# VT_8S_RHS_Bot_V0_1.net
KiCad netlist of a schematic drawn in Altium Designer
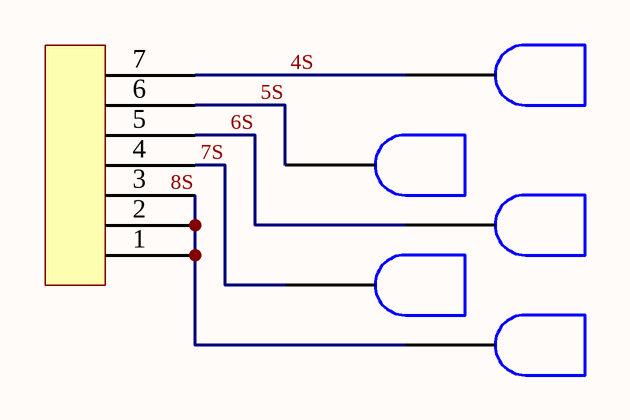
[diagram p0: VT 8S RHS Bot V0.1.SchDoc]

(export (version "E")
  (design (tool "Eeschema 10.0.6"))
  (components
    (comp (ref "J1")
      (value "Voltage Tap")
      (footprint "Voltage Tap")
      (libsource (lib "Voltage Taps V0.1") (part "Voltage Tap"))
    )
    (comp (ref "J2")
      (value "Voltage Tap")
      (footprint "Voltage Tap")
      (libsource (lib "Voltage Taps V0.1") (part "Voltage Tap"))
    )
    (comp (ref "J3")
      (value "Voltage Tap")
      (footprint "Voltage Tap")
      (libsource (lib "Voltage Taps V0.1") (part "Voltage Tap"))
    )
    (comp (ref "J4")
      (value "Voltage Tap")
      (footprint "Voltage Tap")
      (libsource (lib "Voltage Taps V0.1") (part "Voltage Tap"))
    )
    (comp (ref "J5")
      (value "84953-7-FPC")
      (footprint "84953-7 - FPC")
      (description "FPC Connectors, Flex-to-Board, 7 Position, .039 in [1 mm] Centerline, FPC Side Connector")
      (libsource (lib "TE_Con") (part "84953-7-FPC"))
    )
    (comp (ref "J6")
      (value "Voltage Tap")
      (footprint "Voltage Tap")
      (libsource (lib "Voltage Taps V0.1") (part "Voltage Tap"))
    )
  )
  (nets
    (net (code "1") (name "/4S") (class "Default")
      (node (ref "J5") (pin "7") (pintype "passive"))
      (node (ref "J6") (pin "1") (pintype "passive"))
    )
    (net (code "2") (name "/5S") (class "Default")
      (node (ref "J4") (pin "1") (pintype "passive"))
      (node (ref "J5") (pin "6") (pintype "passive"))
    )
    (net (code "3") (name "/6S") (class "Default")
      (node (ref "J3") (pin "1") (pintype "passive"))
      (node (ref "J5") (pin "5") (pintype "passive"))
    )
    (net (code "4") (name "/7S") (class "Default")
      (node (ref "J2") (pin "1") (pintype "passive"))
      (node (ref "J5") (pin "4") (pintype "passive"))
    )
    (net (code "5") (name "/8S") (class "Default")
      (node (ref "J1") (pin "1") (pintype "passive"))
      (node (ref "J5") (pin "1") (pintype "passive"))
      (node (ref "J5") (pin "2") (pintype "passive"))
      (node (ref "J5") (pin "3") (pintype "passive"))
    )
  )
)
